# backplane_v2.net
KiCad netlist of a schematic drawn in EAGLE
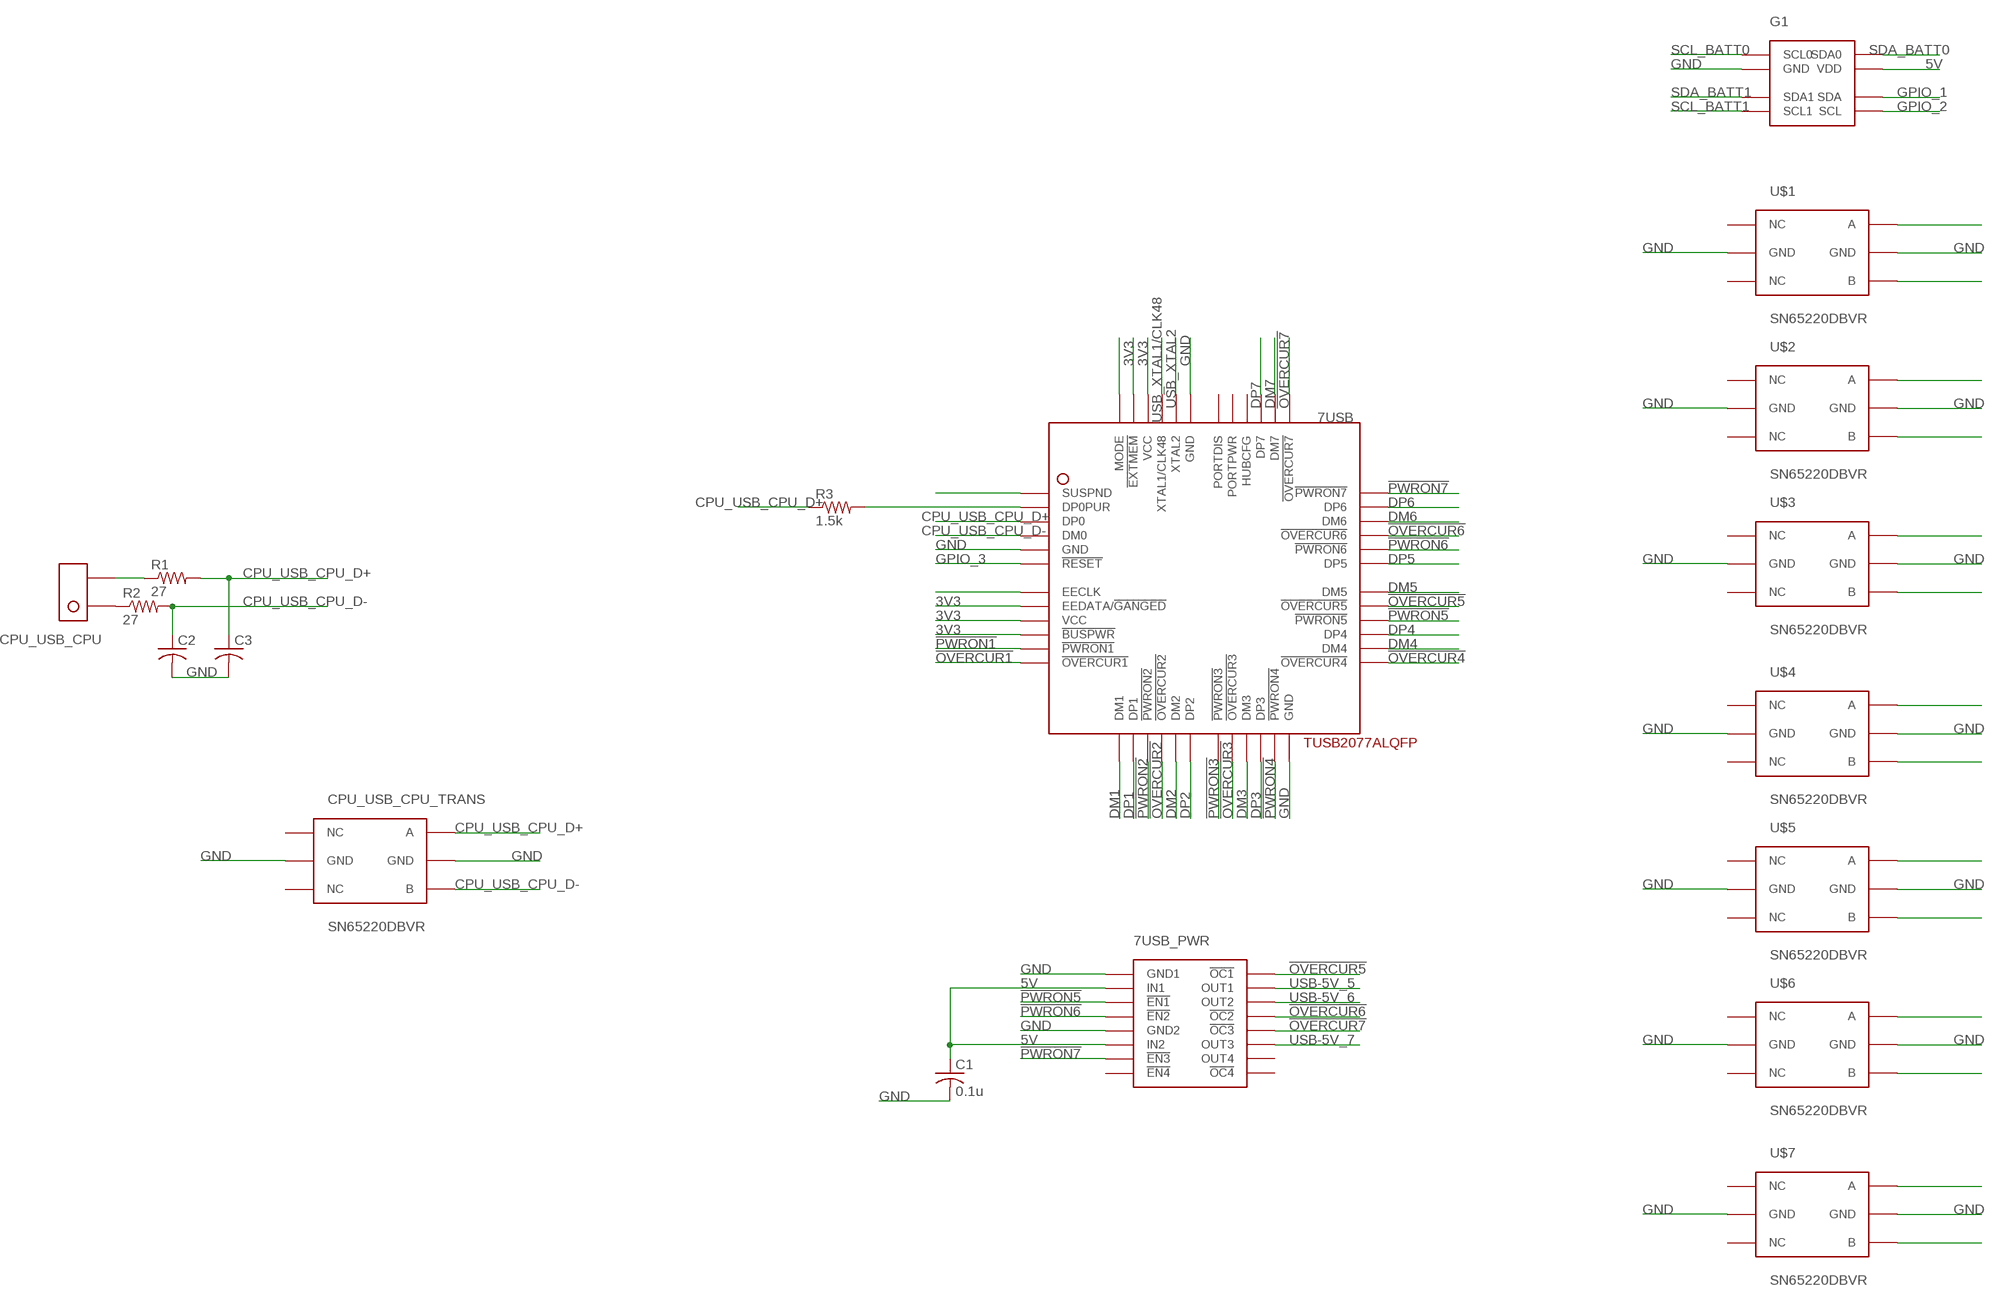
[diagram p0: schematic, sheet 1, part 1 of 2]
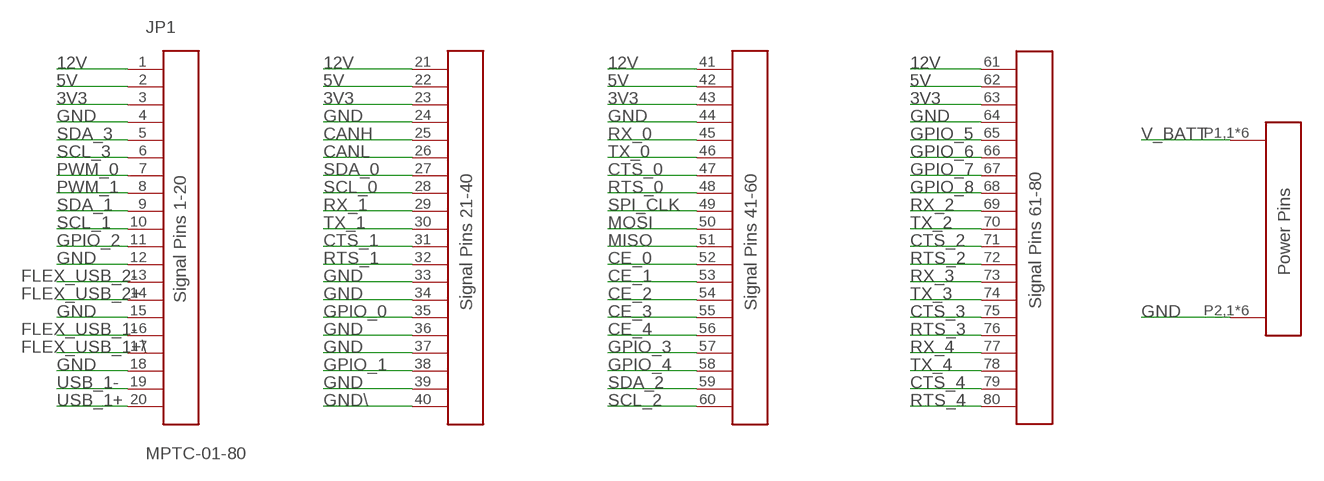
[diagram p1: schematic, sheet 1, part 2 of 2]

(export (version "E")
  (design (tool "Eeschema 10.0.6"))
  (components
    (comp (ref "7USB")
      (value "TUSB2077ALQFP")
      (footprint "eagle-import:48-LQFP_0.5MM_PITCH")
      (libsource (lib "eagle-import") (part "TUSB2077ALQFP"))
    )
    (comp (ref "7USB_PWR")
      (value "TPS2044BBD-SOIC")
      (footprint "eagle-import:TPS2044")
      (libsource (lib "eagle-import") (part "TPS2044BBD-SOIC"))
    )
    (comp (ref "C1")
      (value "0.1u")
      (footprint "eagle-import:C0603")
      (libsource (lib "eagle-import") (part "C-USC0603"))
    )
    (comp (ref "C2")
      (value "C-USC0805")
      (footprint "eagle-import:C0805")
      (libsource (lib "eagle-import") (part "C-USC0805"))
    )
    (comp (ref "C3")
      (value "C-USC0805")
      (footprint "eagle-import:C0805")
      (libsource (lib "eagle-import") (part "C-USC0805"))
    )
    (comp (ref "CPU_USB_CPU")
      (value "KK254_VERT_2PIN22-29-2021")
      (footprint "eagle-import:KK254_VERT_2PIN")
      (libsource (lib "eagle-import") (part "KK254_VERT_2PIN22-29-2021"))
    )
    (comp (ref "CPU_USB_CPU_TRANS")
      (value "SN65220DBVR")
      (footprint "eagle-import:SOT23-6PIN")
      (libsource (lib "eagle-import") (part "SN65220DBVR"))
    )
    (comp (ref "G1")
      (value "PCA9540BTSSOP8")
      (footprint "eagle-import:PCA9540B")
      (libsource (lib "eagle-import") (part "PCA9540BTSSOP8"))
    )
    (comp (ref "JP1")
      (value "MPTC-01-80")
      (footprint "eagle-import:MPTC-01-80")
      (libsource (lib "eagle-import") (part "MPTC-01-80"))
    )
    (comp (ref "R1")
      (value "27")
      (footprint "eagle-import:R0805")
      (libsource (lib "eagle-import") (part "R-US_R0805"))
    )
    (comp (ref "R2")
      (value "27")
      (footprint "eagle-import:R0805")
      (libsource (lib "eagle-import") (part "R-US_R0805"))
    )
    (comp (ref "R3")
      (value "1.5k")
      (footprint "eagle-import:R0805")
      (libsource (lib "eagle-import") (part "R-US_R0805"))
    )
    (comp (ref "U$1")
      (value "SN65220DBVR")
      (footprint "eagle-import:SOT23-6PIN")
      (libsource (lib "eagle-import") (part "SN65220DBVR"))
    )
    (comp (ref "U$2")
      (value "SN65220DBVR")
      (footprint "eagle-import:SOT23-6PIN")
      (libsource (lib "eagle-import") (part "SN65220DBVR"))
    )
    (comp (ref "U$3")
      (value "SN65220DBVR")
      (footprint "eagle-import:SOT23-6PIN")
      (libsource (lib "eagle-import") (part "SN65220DBVR"))
    )
    (comp (ref "U$4")
      (value "SN65220DBVR")
      (footprint "eagle-import:SOT23-6PIN")
      (libsource (lib "eagle-import") (part "SN65220DBVR"))
    )
    (comp (ref "U$5")
      (value "SN65220DBVR")
      (footprint "eagle-import:SOT23-6PIN")
      (libsource (lib "eagle-import") (part "SN65220DBVR"))
    )
    (comp (ref "U$6")
      (value "SN65220DBVR")
      (footprint "eagle-import:SOT23-6PIN")
      (libsource (lib "eagle-import") (part "SN65220DBVR"))
    )
    (comp (ref "U$7")
      (value "SN65220DBVR")
      (footprint "eagle-import:SOT23-6PIN")
      (libsource (lib "eagle-import") (part "SN65220DBVR"))
    )
  )
  (nets
    (net (code "1") (name "/3V3") (class "Default")
      (node (ref "7USB") (pin "P$10") (pinfunction "~{BUSPWR}_P$10") (pintype "bidirectional"))
      (node (ref "7USB") (pin "P$46") (pinfunction "VCC_P$46") (pintype "bidirectional"))
      (node (ref "7USB") (pin "P$47") (pinfunction "~{EXTMEM}_P$47") (pintype "bidirectional"))
      (node (ref "7USB") (pin "P$8") (pinfunction "EEDATA/~{GANGED}_P$8") (pintype "bidirectional"))
      (node (ref "7USB") (pin "P$9") (pinfunction "VCC_P$9") (pintype "bidirectional"))
      (node (ref "JP1") (pin "23") (pinfunction "P$23_23") (pintype "bidirectional"))
      (node (ref "JP1") (pin "3") (pinfunction "P$3_3") (pintype "bidirectional"))
      (node (ref "JP1") (pin "43") (pinfunction "P$43_43") (pintype "bidirectional"))
      (node (ref "JP1") (pin "63") (pinfunction "P$63_63") (pintype "bidirectional"))
    )
    (net (code "2") (name "/5V") (class "Default")
      (node (ref "7USB_PWR") (pin "IN1") (pinfunction "IN1_IN1") (pintype "bidirectional"))
      (node (ref "7USB_PWR") (pin "IN2") (pinfunction "IN2_IN2") (pintype "bidirectional"))
      (node (ref "C1") (pin "1") (pinfunction "1_1") (pintype "passive"))
      (node (ref "G1") (pin "VDD") (pinfunction "VDD_VDD") (pintype "bidirectional"))
      (node (ref "JP1") (pin "2") (pinfunction "P$2_2") (pintype "bidirectional"))
      (node (ref "JP1") (pin "22") (pinfunction "P$22_22") (pintype "bidirectional"))
      (node (ref "JP1") (pin "42") (pinfunction "P$42_42") (pintype "bidirectional"))
      (node (ref "JP1") (pin "62") (pinfunction "P$62_62") (pintype "bidirectional"))
    )
    (net (code "3") (name "/12V") (class "Default")
      (node (ref "JP1") (pin "1") (pinfunction "P$1_1") (pintype "bidirectional"))
      (node (ref "JP1") (pin "21") (pinfunction "P$21_21") (pintype "bidirectional"))
      (node (ref "JP1") (pin "41") (pinfunction "P$41_41") (pintype "bidirectional"))
      (node (ref "JP1") (pin "61") (pinfunction "P$61_61") (pintype "bidirectional"))
    )
    (net (code "4") (name "/CANH") (class "Default")
      (node (ref "JP1") (pin "25") (pinfunction "P$25_25") (pintype "bidirectional"))
    )
    (net (code "5") (name "/CANL") (class "Default")
      (node (ref "JP1") (pin "26") (pinfunction "P$26_26") (pintype "bidirectional"))
    )
    (net (code "6") (name "/CE_0") (class "Default")
      (node (ref "JP1") (pin "52") (pinfunction "P$52_52") (pintype "bidirectional"))
    )
    (net (code "7") (name "/CE_1") (class "Default")
      (node (ref "JP1") (pin "53") (pinfunction "P$53_53") (pintype "bidirectional"))
    )
    (net (code "8") (name "/CE_2") (class "Default")
      (node (ref "JP1") (pin "54") (pinfunction "P$54_54") (pintype "bidirectional"))
    )
    (net (code "9") (name "/CE_3") (class "Default")
      (node (ref "JP1") (pin "55") (pinfunction "P$55_55") (pintype "bidirectional"))
    )
    (net (code "10") (name "/CE_4") (class "Default")
      (node (ref "JP1") (pin "56") (pinfunction "P$56_56") (pintype "bidirectional"))
    )
    (net (code "11") (name "/CPU_USB_CPU_D+") (class "Default")
      (node (ref "7USB") (pin "P$3") (pinfunction "DP0_P$3") (pintype "bidirectional"))
      (node (ref "C3") (pin "1") (pinfunction "1_1") (pintype "passive"))
      (node (ref "CPU_USB_CPU_TRANS") (pin "P$6") (pinfunction "A_P$6") (pintype "bidirectional"))
      (node (ref "R1") (pin "2") (pinfunction "2_2") (pintype "passive"))
      (node (ref "R3") (pin "1") (pinfunction "1_1") (pintype "passive"))
    )
    (net (code "12") (name "/CPU_USB_CPU_D-") (class "Default")
      (node (ref "7USB") (pin "P$4") (pinfunction "DM0_P$4") (pintype "bidirectional"))
      (node (ref "C2") (pin "1") (pinfunction "1_1") (pintype "passive"))
      (node (ref "CPU_USB_CPU_TRANS") (pin "P$4") (pinfunction "B_P$4") (pintype "bidirectional"))
      (node (ref "R2") (pin "2") (pinfunction "2_2") (pintype "passive"))
    )
    (net (code "13") (name "/CTS_0") (class "Default")
      (node (ref "JP1") (pin "47") (pinfunction "P$47_47") (pintype "bidirectional"))
    )
    (net (code "14") (name "/CTS_1") (class "Default")
      (node (ref "JP1") (pin "31") (pinfunction "P$31_31") (pintype "bidirectional"))
    )
    (net (code "15") (name "/CTS_2") (class "Default")
      (node (ref "JP1") (pin "71") (pinfunction "P$71_71") (pintype "bidirectional"))
    )
    (net (code "16") (name "/CTS_3") (class "Default")
      (node (ref "JP1") (pin "75") (pinfunction "P$75_75") (pintype "bidirectional"))
    )
    (net (code "17") (name "/CTS_4") (class "Default")
      (node (ref "JP1") (pin "79") (pinfunction "P$79_79") (pintype "bidirectional"))
    )
    (net (code "18") (name "/DM1") (class "Default")
      (node (ref "7USB") (pin "P$13") (pinfunction "DM1_P$13") (pintype "bidirectional"))
    )
    (net (code "19") (name "/DM2") (class "Default")
      (node (ref "7USB") (pin "P$17") (pinfunction "DM2_P$17") (pintype "bidirectional"))
    )
    (net (code "20") (name "/DM3") (class "Default")
      (node (ref "7USB") (pin "P$21") (pinfunction "DM3_P$21") (pintype "bidirectional"))
    )
    (net (code "21") (name "/DM4") (class "Default")
      (node (ref "7USB") (pin "P$26") (pinfunction "DM4_P$26") (pintype "bidirectional"))
    )
    (net (code "22") (name "/DM5") (class "Default")
      (node (ref "7USB") (pin "P$30") (pinfunction "DM5_P$30") (pintype "bidirectional"))
    )
    (net (code "23") (name "/DM6") (class "Default")
      (node (ref "7USB") (pin "P$34") (pinfunction "DM6_P$34") (pintype "bidirectional"))
    )
    (net (code "24") (name "/DM7") (class "Default")
      (node (ref "7USB") (pin "P$38") (pinfunction "DM7_P$38") (pintype "bidirectional"))
    )
    (net (code "25") (name "/DP1") (class "Default")
      (node (ref "7USB") (pin "P$14") (pinfunction "DP1_P$14") (pintype "bidirectional"))
    )
    (net (code "26") (name "/DP2") (class "Default")
      (node (ref "7USB") (pin "P$18") (pinfunction "DP2_P$18") (pintype "bidirectional"))
    )
    (net (code "27") (name "/DP3") (class "Default")
      (node (ref "7USB") (pin "P$22") (pinfunction "DP3_P$22") (pintype "bidirectional"))
    )
    (net (code "28") (name "/DP4") (class "Default")
      (node (ref "7USB") (pin "P$27") (pinfunction "DP4_P$27") (pintype "bidirectional"))
    )
    (net (code "29") (name "/DP5") (class "Default")
      (node (ref "7USB") (pin "P$31") (pinfunction "DP5_P$31") (pintype "bidirectional"))
    )
    (net (code "30") (name "/DP6") (class "Default")
      (node (ref "7USB") (pin "P$35") (pinfunction "DP6_P$35") (pintype "bidirectional"))
    )
    (net (code "31") (name "/DP7") (class "Default")
      (node (ref "7USB") (pin "P$39") (pinfunction "DP7_P$39") (pintype "bidirectional"))
    )
    (net (code "32") (name "/FLEX_USB_1+\\") (class "Default")
      (node (ref "JP1") (pin "17") (pinfunction "P$17_17") (pintype "bidirectional"))
    )
    (net (code "33") (name "/FLEX_USB_1-") (class "Default")
      (node (ref "JP1") (pin "16") (pinfunction "P$16_16") (pintype "bidirectional"))
    )
    (net (code "34") (name "/FLEX_USB_2+") (class "Default")
      (node (ref "JP1") (pin "14") (pinfunction "P$14_14") (pintype "bidirectional"))
    )
    (net (code "35") (name "/FLEX_USB_2-") (class "Default")
      (node (ref "JP1") (pin "13") (pinfunction "P$13_13") (pintype "bidirectional"))
    )
    (net (code "36") (name "/GND") (class "Default")
      (node (ref "7USB") (pin "P$24") (pinfunction "GND_P$24") (pintype "bidirectional"))
      (node (ref "7USB") (pin "P$43") (pinfunction "GND_P$43") (pintype "bidirectional"))
      (node (ref "7USB") (pin "P$48") (pinfunction "MODE_P$48") (pintype "bidirectional"))
      (node (ref "7USB") (pin "P$5") (pinfunction "GND_P$5") (pintype "bidirectional"))
      (node (ref "7USB_PWR") (pin "GND1") (pinfunction "GND1_GND1") (pintype "bidirectional"))
      (node (ref "7USB_PWR") (pin "GND2") (pinfunction "GND2_GND2") (pintype "bidirectional"))
      (node (ref "C1") (pin "2") (pinfunction "2_2") (pintype "passive"))
      (node (ref "C2") (pin "2") (pinfunction "2_2") (pintype "passive"))
      (node (ref "C3") (pin "2") (pinfunction "2_2") (pintype "passive"))
      (node (ref "CPU_USB_CPU_TRANS") (pin "P$2") (pinfunction "GND_P$2") (pintype "bidirectional"))
      (node (ref "CPU_USB_CPU_TRANS") (pin "P$5") (pinfunction "GND_P$5") (pintype "bidirectional"))
      (node (ref "G1") (pin "GND") (pinfunction "GND_GND") (pintype "bidirectional"))
      (node (ref "JP1") (pin "12") (pinfunction "P$12_12") (pintype "bidirectional"))
      (node (ref "JP1") (pin "15") (pinfunction "P$15_15") (pintype "bidirectional"))
      (node (ref "JP1") (pin "18") (pinfunction "P$18_18") (pintype "bidirectional"))
      (node (ref "JP1") (pin "24") (pinfunction "P$24_24") (pintype "bidirectional"))
      (node (ref "JP1") (pin "33") (pinfunction "P$33_33") (pintype "bidirectional"))
      (node (ref "JP1") (pin "34") (pinfunction "P$34_34") (pintype "bidirectional"))
      (node (ref "JP1") (pin "36") (pinfunction "P$36_36") (pintype "bidirectional"))
      (node (ref "JP1") (pin "37") (pinfunction "P$37_37") (pintype "bidirectional"))
      (node (ref "JP1") (pin "39") (pinfunction "P$39_39") (pintype "bidirectional"))
      (node (ref "JP1") (pin "4") (pinfunction "P$4_4") (pintype "bidirectional"))
      (node (ref "JP1") (pin "44") (pinfunction "P$44_44") (pintype "bidirectional"))
      (node (ref "JP1") (pin "64") (pinfunction "P$64_64") (pintype "bidirectional"))
      (node (ref "JP1") (pin "P2,1") (pinfunction "POWER2_P2,1") (pintype "bidirectional"))
      (node (ref "JP1") (pin "P2,2") (pinfunction "POWER2_P2,2") (pintype "bidirectional"))
      (node (ref "JP1") (pin "P2,3") (pinfunction "POWER2_P2,3") (pintype "bidirectional"))
      (node (ref "JP1") (pin "P2,4") (pinfunction "POWER2_P2,4") (pintype "bidirectional"))
      (node (ref "JP1") (pin "P2,5") (pinfunction "POWER2_P2,5") (pintype "bidirectional"))
      (node (ref "JP1") (pin "P2,6") (pinfunction "POWER2_P2,6") (pintype "bidirectional"))
      (node (ref "U$1") (pin "P$2") (pinfunction "GND_P$2") (pintype "bidirectional"))
      (node (ref "U$1") (pin "P$5") (pinfunction "GND_P$5") (pintype "bidirectional"))
      (node (ref "U$2") (pin "P$2") (pinfunction "GND_P$2") (pintype "bidirectional"))
      (node (ref "U$2") (pin "P$5") (pinfunction "GND_P$5") (pintype "bidirectional"))
      (node (ref "U$3") (pin "P$2") (pinfunction "GND_P$2") (pintype "bidirectional"))
      (node (ref "U$3") (pin "P$5") (pinfunction "GND_P$5") (pintype "bidirectional"))
      (node (ref "U$4") (pin "P$2") (pinfunction "GND_P$2") (pintype "bidirectional"))
      (node (ref "U$4") (pin "P$5") (pinfunction "GND_P$5") (pintype "bidirectional"))
      (node (ref "U$5") (pin "P$2") (pinfunction "GND_P$2") (pintype "bidirectional"))
      (node (ref "U$5") (pin "P$5") (pinfunction "GND_P$5") (pintype "bidirectional"))
      (node (ref "U$6") (pin "P$2") (pinfunction "GND_P$2") (pintype "bidirectional"))
      (node (ref "U$6") (pin "P$5") (pinfunction "GND_P$5") (pintype "bidirectional"))
      (node (ref "U$7") (pin "P$2") (pinfunction "GND_P$2") (pintype "bidirectional"))
      (node (ref "U$7") (pin "P$5") (pinfunction "GND_P$5") (pintype "bidirectional"))
    )
    (net (code "37") (name "/GND\\") (class "Default")
      (node (ref "JP1") (pin "40") (pinfunction "P$40_40") (pintype "bidirectional"))
    )
    (net (code "38") (name "/GPIO_0") (class "Default")
      (node (ref "JP1") (pin "35") (pinfunction "P$35_35") (pintype "bidirectional"))
    )
    (net (code "39") (name "/GPIO_1") (class "Default")
      (node (ref "G1") (pin "SDA") (pinfunction "SDA_SDA") (pintype "bidirectional"))
      (node (ref "JP1") (pin "38") (pinfunction "P$38_38") (pintype "bidirectional"))
    )
    (net (code "40") (name "/GPIO_2") (class "Default")
      (node (ref "G1") (pin "SCL") (pinfunction "SCL_SCL") (pintype "bidirectional"))
      (node (ref "JP1") (pin "11") (pinfunction "P$11_11") (pintype "bidirectional"))
    )
    (net (code "41") (name "/GPIO_3") (class "Default")
      (node (ref "7USB") (pin "P$6") (pinfunction "~{RESET}_P$6") (pintype "bidirectional"))
      (node (ref "JP1") (pin "57") (pinfunction "P$57_57") (pintype "bidirectional"))
    )
    (net (code "42") (name "/GPIO_4") (class "Default")
      (node (ref "JP1") (pin "58") (pinfunction "P$58_58") (pintype "bidirectional"))
    )
    (net (code "43") (name "/GPIO_5") (class "Default")
      (node (ref "JP1") (pin "65") (pinfunction "P$65_65") (pintype "bidirectional"))
    )
    (net (code "44") (name "/GPIO_6") (class "Default")
      (node (ref "JP1") (pin "66") (pinfunction "P$66_66") (pintype "bidirectional"))
    )
    (net (code "45") (name "/GPIO_7") (class "Default")
      (node (ref "JP1") (pin "67") (pinfunction "P$67_67") (pintype "bidirectional"))
    )
    (net (code "46") (name "/GPIO_8") (class "Default")
      (node (ref "JP1") (pin "68") (pinfunction "P$68_68") (pintype "bidirectional"))
    )
    (net (code "47") (name "/MISO") (class "Default")
      (node (ref "JP1") (pin "51") (pinfunction "P$51_51") (pintype "bidirectional"))
    )
    (net (code "48") (name "/MOSI") (class "Default")
      (node (ref "JP1") (pin "50") (pinfunction "P$50_50") (pintype "bidirectional"))
    )
    (net (code "49") (name "/PWM_0") (class "Default")
      (node (ref "JP1") (pin "7") (pinfunction "P$7_7") (pintype "bidirectional"))
    )
    (net (code "50") (name "/PWM_1") (class "Default")
      (node (ref "JP1") (pin "8") (pinfunction "P$8_8") (pintype "bidirectional"))
    )
    (net (code "51") (name "/RTS_0") (class "Default")
      (node (ref "JP1") (pin "48") (pinfunction "P$48_48") (pintype "bidirectional"))
    )
    (net (code "52") (name "/RTS_1") (class "Default")
      (node (ref "JP1") (pin "32") (pinfunction "P$32_32") (pintype "bidirectional"))
    )
    (net (code "53") (name "/RTS_2") (class "Default")
      (node (ref "JP1") (pin "72") (pinfunction "P$72_72") (pintype "bidirectional"))
    )
    (net (code "54") (name "/RTS_3") (class "Default")
      (node (ref "JP1") (pin "76") (pinfunction "P$76_76") (pintype "bidirectional"))
    )
    (net (code "55") (name "/RTS_4") (class "Default")
      (node (ref "JP1") (pin "80") (pinfunction "P$80_80") (pintype "bidirectional"))
    )
    (net (code "56") (name "/RX_0") (class "Default")
      (node (ref "JP1") (pin "45") (pinfunction "P$45_45") (pintype "bidirectional"))
    )
    (net (code "57") (name "/RX_1") (class "Default")
      (node (ref "JP1") (pin "29") (pinfunction "P$29_29") (pintype "bidirectional"))
    )
    (net (code "58") (name "/RX_2") (class "Default")
      (node (ref "JP1") (pin "69") (pinfunction "P$69_69") (pintype "bidirectional"))
    )
    (net (code "59") (name "/RX_3") (class "Default")
      (node (ref "JP1") (pin "73") (pinfunction "P$73_73") (pintype "bidirectional"))
    )
    (net (code "60") (name "/RX_4") (class "Default")
      (node (ref "JP1") (pin "77") (pinfunction "P$77_77") (pintype "bidirectional"))
    )
    (net (code "61") (name "/SCL_0") (class "Default")
      (node (ref "JP1") (pin "28") (pinfunction "P$28_28") (pintype "bidirectional"))
    )
    (net (code "62") (name "/SCL_1") (class "Default")
      (node (ref "JP1") (pin "10") (pinfunction "P$10_10") (pintype "bidirectional"))
    )
    (net (code "63") (name "/SCL_2") (class "Default")
      (node (ref "JP1") (pin "60") (pinfunction "P$60_60") (pintype "bidirectional"))
    )
    (net (code "64") (name "/SCL_3") (class "Default")
      (node (ref "JP1") (pin "6") (pinfunction "P$6_6") (pintype "bidirectional"))
    )
    (net (code "65") (name "/SCL_BATT0") (class "Default")
      (node (ref "G1") (pin "SCL0") (pinfunction "SCL0_SCL0") (pintype "bidirectional"))
    )
    (net (code "66") (name "/SCL_BATT1") (class "Default")
      (node (ref "G1") (pin "SCL1") (pinfunction "SCL1_SCL1") (pintype "bidirectional"))
    )
    (net (code "67") (name "/SDA_0") (class "Default")
      (node (ref "JP1") (pin "27") (pinfunction "P$27_27") (pintype "bidirectional"))
    )
    (net (code "68") (name "/SDA_1") (class "Default")
      (node (ref "JP1") (pin "9") (pinfunction "P$9_9") (pintype "bidirectional"))
    )
    (net (code "69") (name "/SDA_2") (class "Default")
      (node (ref "JP1") (pin "59") (pinfunction "P$59_59") (pintype "bidirectional"))
    )
    (net (code "70") (name "/SDA_3") (class "Default")
      (node (ref "JP1") (pin "5") (pinfunction "P$5_5") (pintype "bidirectional"))
    )
    (net (code "71") (name "/SDA_BATT0") (class "Default")
      (node (ref "G1") (pin "SDA0") (pinfunction "SDA0_SDA0") (pintype "bidirectional"))
    )
    (net (code "72") (name "/SDA_BATT1") (class "Default")
      (node (ref "G1") (pin "SDA1") (pinfunction "SDA1_SDA1") (pintype "bidirectional"))
    )
    (net (code "73") (name "/SPI_CLK") (class "Default")
      (node (ref "JP1") (pin "49") (pinfunction "P$49_49") (pintype "bidirectional"))
    )
    (net (code "74") (name "/TX_0") (class "Default")
      (node (ref "JP1") (pin "46") (pinfunction "P$46_46") (pintype "bidirectional"))
    )
    (net (code "75") (name "/TX_1") (class "Default")
      (node (ref "JP1") (pin "30") (pinfunction "P$30_30") (pintype "bidirectional"))
    )
    (net (code "76") (name "/TX_2") (class "Default")
      (node (ref "JP1") (pin "70") (pinfunction "P$70_70") (pintype "bidirectional"))
    )
    (net (code "77") (name "/TX_3") (class "Default")
      (node (ref "JP1") (pin "74") (pinfunction "P$74_74") (pintype "bidirectional"))
    )
    (net (code "78") (name "/TX_4") (class "Default")
      (node (ref "JP1") (pin "78") (pinfunction "P$78_78") (pintype "bidirectional"))
    )
    (net (code "79") (name "/USB-5V_5") (class "Default")
      (node (ref "7USB_PWR") (pin "OUT1") (pinfunction "OUT1_OUT1") (pintype "bidirectional"))
    )
    (net (code "80") (name "/USB-5V_6") (class "Default")
      (node (ref "7USB_PWR") (pin "OUT2") (pinfunction "OUT2_OUT2") (pintype "bidirectional"))
    )
    (net (code "81") (name "/USB-5V_7") (class "Default")
      (node (ref "7USB_PWR") (pin "OUT3") (pinfunction "OUT3_OUT3") (pintype "bidirectional"))
    )
    (net (code "82") (name "/USB_1+") (class "Default")
      (node (ref "JP1") (pin "20") (pinfunction "P$20_20") (pintype "bidirectional"))
    )
    (net (code "83") (name "/USB_1-") (class "Default")
      (node (ref "JP1") (pin "19") (pinfunction "P$19_19") (pintype "bidirectional"))
    )
    (net (code "84") (name "/USB_XTAL1{slash}CLK48") (class "Default")
      (node (ref "7USB") (pin "P$45") (pinfunction "XTAL1/CLK48_P$45") (pintype "bidirectional"))
    )
    (net (code "85") (name "/USB_XTAL2") (class "Default")
      (node (ref "7USB") (pin "P$44") (pinfunction "XTAL2_P$44") (pintype "bidirectional"))
    )
    (net (code "86") (name "/V_BATT") (class "Default")
      (node (ref "JP1") (pin "P1,1") (pinfunction "POWER1_P1,1") (pintype "bidirectional"))
      (node (ref "JP1") (pin "P1,2") (pinfunction "POWER1_P1,2") (pintype "bidirectional"))
      (node (ref "JP1") (pin "P1,3") (pinfunction "POWER1_P1,3") (pintype "bidirectional"))
      (node (ref "JP1") (pin "P1,4") (pinfunction "POWER1_P1,4") (pintype "bidirectional"))
      (node (ref "JP1") (pin "P1,5") (pinfunction "POWER1_P1,5") (pintype "bidirectional"))
      (node (ref "JP1") (pin "P1,6") (pinfunction "POWER1_P1,6") (pintype "bidirectional"))
    )
    (net (code "87") (name "/~{OVERCUR1}") (class "Default")
      (node (ref "7USB") (pin "P$12") (pinfunction "~{OVERCUR1}_P$12") (pintype "bidirectional"))
    )
    (net (code "88") (name "/~{OVERCUR2}") (class "Default")
      (node (ref "7USB") (pin "P$16") (pinfunction "~{OVERCUR2}_P$16") (pintype "bidirectional"))
    )
    (net (code "89") (name "/~{OVERCUR3}") (class "Default")
      (node (ref "7USB") (pin "P$20") (pinfunction "~{OVERCUR3}_P$20") (pintype "bidirectional"))
    )
    (net (code "90") (name "/~{OVERCUR4}") (class "Default")
      (node (ref "7USB") (pin "P$25") (pinfunction "~{OVERCUR4}_P$25") (pintype "bidirectional"))
    )
    (net (code "91") (name "/~{OVERCUR5}") (class "Default")
      (node (ref "7USB") (pin "P$29") (pinfunction "~{OVERCUR5}_P$29") (pintype "bidirectional"))
      (node (ref "7USB_PWR") (pin "!OC1!") (pinfunction "~{OC1}_!OC1!") (pintype "bidirectional"))
    )
    (net (code "92") (name "/~{OVERCUR6}") (class "Default")
      (node (ref "7USB") (pin "P$33") (pinfunction "~{OVERCUR6}_P$33") (pintype "bidirectional"))
      (node (ref "7USB_PWR") (pin "!OC2!") (pinfunction "~{OC2}_!OC2!") (pintype "bidirectional"))
    )
    (net (code "93") (name "/~{OVERCUR7}") (class "Default")
      (node (ref "7USB") (pin "P$37") (pinfunction "~{OVERCUR7}_P$37") (pintype "bidirectional"))
      (node (ref "7USB_PWR") (pin "!OC3!") (pinfunction "~{OC3}_!OC3!") (pintype "bidirectional"))
    )
    (net (code "94") (name "/~{PWRON1}") (class "Default")
      (node (ref "7USB") (pin "P$11") (pinfunction "~{PWRON1}_P$11") (pintype "bidirectional"))
    )
    (net (code "95") (name "/~{PWRON2}") (class "Default")
      (node (ref "7USB") (pin "P$15") (pinfunction "~{PWRON2}_P$15") (pintype "bidirectional"))
    )
    (net (code "96") (name "/~{PWRON3}") (class "Default")
      (node (ref "7USB") (pin "P$19") (pinfunction "~{PWRON3}_P$19") (pintype "bidirectional"))
    )
    (net (code "97") (name "/~{PWRON4}") (class "Default")
      (node (ref "7USB") (pin "P$23") (pinfunction "~{PWRON4}_P$23") (pintype "bidirectional"))
    )
    (net (code "98") (name "/~{PWRON5}") (class "Default")
      (node (ref "7USB") (pin "P$28") (pinfunction "~{PWRON5}_P$28") (pintype "bidirectional"))
      (node (ref "7USB_PWR") (pin "!EN1!") (pinfunction "~{EN1}_!EN1!") (pintype "bidirectional"))
    )
    (net (code "99") (name "/~{PWRON6}") (class "Default")
      (node (ref "7USB") (pin "P$32") (pinfunction "~{PWRON6}_P$32") (pintype "bidirectional"))
      (node (ref "7USB_PWR") (pin "!EN2!") (pinfunction "~{EN2}_!EN2!") (pintype "bidirectional"))
    )
    (net (code "100") (name "/~{PWRON7}") (class "Default")
      (node (ref "7USB") (pin "P$36") (pinfunction "~{PWRON7}_P$36") (pintype "bidirectional"))
      (node (ref "7USB_PWR") (pin "!EN3!") (pinfunction "~{EN3}_!EN3!") (pintype "bidirectional"))
    )
    (net (code "101") (name "Net-(7USB-DP0PUR)") (class "Default")
      (node (ref "7USB") (pin "P$2") (pinfunction "DP0PUR_P$2") (pintype "bidirectional"))
      (node (ref "R3") (pin "2") (pinfunction "2_2") (pintype "passive"))
    )
    (net (code "102") (name "Net-(CPU_USB_CPU-PadP$1)") (class "Default")
      (node (ref "CPU_USB_CPU") (pin "P$1") (pinfunction "P$1_P$1") (pintype "bidirectional"))
      (node (ref "R2") (pin "1") (pinfunction "1_1") (pintype "passive"))
    )
    (net (code "103") (name "Net-(CPU_USB_CPU-PadP$2)") (class "Default")
      (node (ref "CPU_USB_CPU") (pin "P$2") (pinfunction "P$2_P$2") (pintype "bidirectional"))
      (node (ref "R1") (pin "1") (pinfunction "1_1") (pintype "passive"))
    )
    (net (code "104") (name "unconnected-(7USB-EECLK-PadP$7)") (class "Default")
      (node (ref "7USB") (pin "P$7") (pinfunction "EECLK_P$7") (pintype "bidirectional"))
    )
    (net (code "105") (name "unconnected-(7USB-HUBCFG-PadP$40)") (class "Default")
      (node (ref "7USB") (pin "P$40") (pinfunction "HUBCFG_P$40") (pintype "bidirectional"))
    )
    (net (code "106") (name "unconnected-(7USB-PORTDIS-PadP$42)") (class "Default")
      (node (ref "7USB") (pin "P$42") (pinfunction "PORTDIS_P$42") (pintype "bidirectional"))
    )
    (net (code "107") (name "unconnected-(7USB-PORTPWR-PadP$41)") (class "Default")
      (node (ref "7USB") (pin "P$41") (pinfunction "PORTPWR_P$41") (pintype "bidirectional"))
    )
    (net (code "108") (name "unconnected-(7USB-SUSPND-PadP$1)") (class "Default")
      (node (ref "7USB") (pin "P$1") (pinfunction "SUSPND_P$1") (pintype "bidirectional"))
    )
    (net (code "109") (name "unconnected-(7USB_PWR-PadOUT4)") (class "Default")
      (node (ref "7USB_PWR") (pin "OUT4") (pinfunction "OUT4_OUT4") (pintype "bidirectional"))
    )
    (net (code "110") (name "unconnected-(7USB_PWR-~{EN4}-Pad!EN4!)") (class "Default")
      (node (ref "7USB_PWR") (pin "!EN4!") (pinfunction "~{EN4}_!EN4!") (pintype "bidirectional"))
    )
    (net (code "111") (name "unconnected-(7USB_PWR-~{OC4}-Pad!OC4!)") (class "Default")
      (node (ref "7USB_PWR") (pin "!OC4!") (pinfunction "~{OC4}_!OC4!") (pintype "bidirectional"))
    )
    (net (code "112") (name "unconnected-(CPU_USB_CPU_TRANS-NC-PadP$1)") (class "Default")
      (node (ref "CPU_USB_CPU_TRANS") (pin "P$1") (pinfunction "NC_P$1") (pintype "bidirectional"))
    )
    (net (code "113") (name "unconnected-(CPU_USB_CPU_TRANS-NC-PadP$3)") (class "Default")
      (node (ref "CPU_USB_CPU_TRANS") (pin "P$3") (pinfunction "NC_P$3") (pintype "bidirectional"))
    )
    (net (code "114") (name "unconnected-(U$1-A-PadP$6)") (class "Default")
      (node (ref "U$1") (pin "P$6") (pinfunction "A_P$6") (pintype "bidirectional"))
    )
    (net (code "115") (name "unconnected-(U$1-B-PadP$4)") (class "Default")
      (node (ref "U$1") (pin "P$4") (pinfunction "B_P$4") (pintype "bidirectional"))
    )
    (net (code "116") (name "unconnected-(U$1-NC-PadP$1)") (class "Default")
      (node (ref "U$1") (pin "P$1") (pinfunction "NC_P$1") (pintype "bidirectional"))
    )
    (net (code "117") (name "unconnected-(U$1-NC-PadP$3)") (class "Default")
      (node (ref "U$1") (pin "P$3") (pinfunction "NC_P$3") (pintype "bidirectional"))
    )
    (net (code "118") (name "unconnected-(U$2-A-PadP$6)") (class "Default")
      (node (ref "U$2") (pin "P$6") (pinfunction "A_P$6") (pintype "bidirectional"))
    )
    (net (code "119") (name "unconnected-(U$2-B-PadP$4)") (class "Default")
      (node (ref "U$2") (pin "P$4") (pinfunction "B_P$4") (pintype "bidirectional"))
    )
    (net (code "120") (name "unconnected-(U$2-NC-PadP$1)") (class "Default")
      (node (ref "U$2") (pin "P$1") (pinfunction "NC_P$1") (pintype "bidirectional"))
    )
    (net (code "121") (name "unconnected-(U$2-NC-PadP$3)") (class "Default")
      (node (ref "U$2") (pin "P$3") (pinfunction "NC_P$3") (pintype "bidirectional"))
    )
    (net (code "122") (name "unconnected-(U$3-A-PadP$6)") (class "Default")
      (node (ref "U$3") (pin "P$6") (pinfunction "A_P$6") (pintype "bidirectional"))
    )
    (net (code "123") (name "unconnected-(U$3-B-PadP$4)") (class "Default")
      (node (ref "U$3") (pin "P$4") (pinfunction "B_P$4") (pintype "bidirectional"))
    )
    (net (code "124") (name "unconnected-(U$3-NC-PadP$1)") (class "Default")
      (node (ref "U$3") (pin "P$1") (pinfunction "NC_P$1") (pintype "bidirectional"))
    )
    (net (code "125") (name "unconnected-(U$3-NC-PadP$3)") (class "Default")
      (node (ref "U$3") (pin "P$3") (pinfunction "NC_P$3") (pintype "bidirectional"))
    )
    (net (code "126") (name "unconnected-(U$4-A-PadP$6)") (class "Default")
      (node (ref "U$4") (pin "P$6") (pinfunction "A_P$6") (pintype "bidirectional"))
    )
    (net (code "127") (name "unconnected-(U$4-B-PadP$4)") (class "Default")
      (node (ref "U$4") (pin "P$4") (pinfunction "B_P$4") (pintype "bidirectional"))
    )
    (net (code "128") (name "unconnected-(U$4-NC-PadP$1)") (class "Default")
      (node (ref "U$4") (pin "P$1") (pinfunction "NC_P$1") (pintype "bidirectional"))
    )
    (net (code "129") (name "unconnected-(U$4-NC-PadP$3)") (class "Default")
      (node (ref "U$4") (pin "P$3") (pinfunction "NC_P$3") (pintype "bidirectional"))
    )
    (net (code "130") (name "unconnected-(U$5-A-PadP$6)") (class "Default")
      (node (ref "U$5") (pin "P$6") (pinfunction "A_P$6") (pintype "bidirectional"))
    )
    (net (code "131") (name "unconnected-(U$5-B-PadP$4)") (class "Default")
      (node (ref "U$5") (pin "P$4") (pinfunction "B_P$4") (pintype "bidirectional"))
    )
    (net (code "132") (name "unconnected-(U$5-NC-PadP$1)") (class "Default")
      (node (ref "U$5") (pin "P$1") (pinfunction "NC_P$1") (pintype "bidirectional"))
    )
    (net (code "133") (name "unconnected-(U$5-NC-PadP$3)") (class "Default")
      (node (ref "U$5") (pin "P$3") (pinfunction "NC_P$3") (pintype "bidirectional"))
    )
    (net (code "134") (name "unconnected-(U$6-A-PadP$6)") (class "Default")
      (node (ref "U$6") (pin "P$6") (pinfunction "A_P$6") (pintype "bidirectional"))
    )
    (net (code "135") (name "unconnected-(U$6-B-PadP$4)") (class "Default")
      (node (ref "U$6") (pin "P$4") (pinfunction "B_P$4") (pintype "bidirectional"))
    )
    (net (code "136") (name "unconnected-(U$6-NC-PadP$1)") (class "Default")
      (node (ref "U$6") (pin "P$1") (pinfunction "NC_P$1") (pintype "bidirectional"))
    )
    (net (code "137") (name "unconnected-(U$6-NC-PadP$3)") (class "Default")
      (node (ref "U$6") (pin "P$3") (pinfunction "NC_P$3") (pintype "bidirectional"))
    )
    (net (code "138") (name "unconnected-(U$7-A-PadP$6)") (class "Default")
      (node (ref "U$7") (pin "P$6") (pinfunction "A_P$6") (pintype "bidirectional"))
    )
    (net (code "139") (name "unconnected-(U$7-B-PadP$4)") (class "Default")
      (node (ref "U$7") (pin "P$4") (pinfunction "B_P$4") (pintype "bidirectional"))
    )
    (net (code "140") (name "unconnected-(U$7-NC-PadP$1)") (class "Default")
      (node (ref "U$7") (pin "P$1") (pinfunction "NC_P$1") (pintype "bidirectional"))
    )
    (net (code "141") (name "unconnected-(U$7-NC-PadP$3)") (class "Default")
      (node (ref "U$7") (pin "P$3") (pinfunction "NC_P$3") (pintype "bidirectional"))
    )
  )
)
